# Alim.net
KiCad netlist of a schematic drawn in Altium Designer
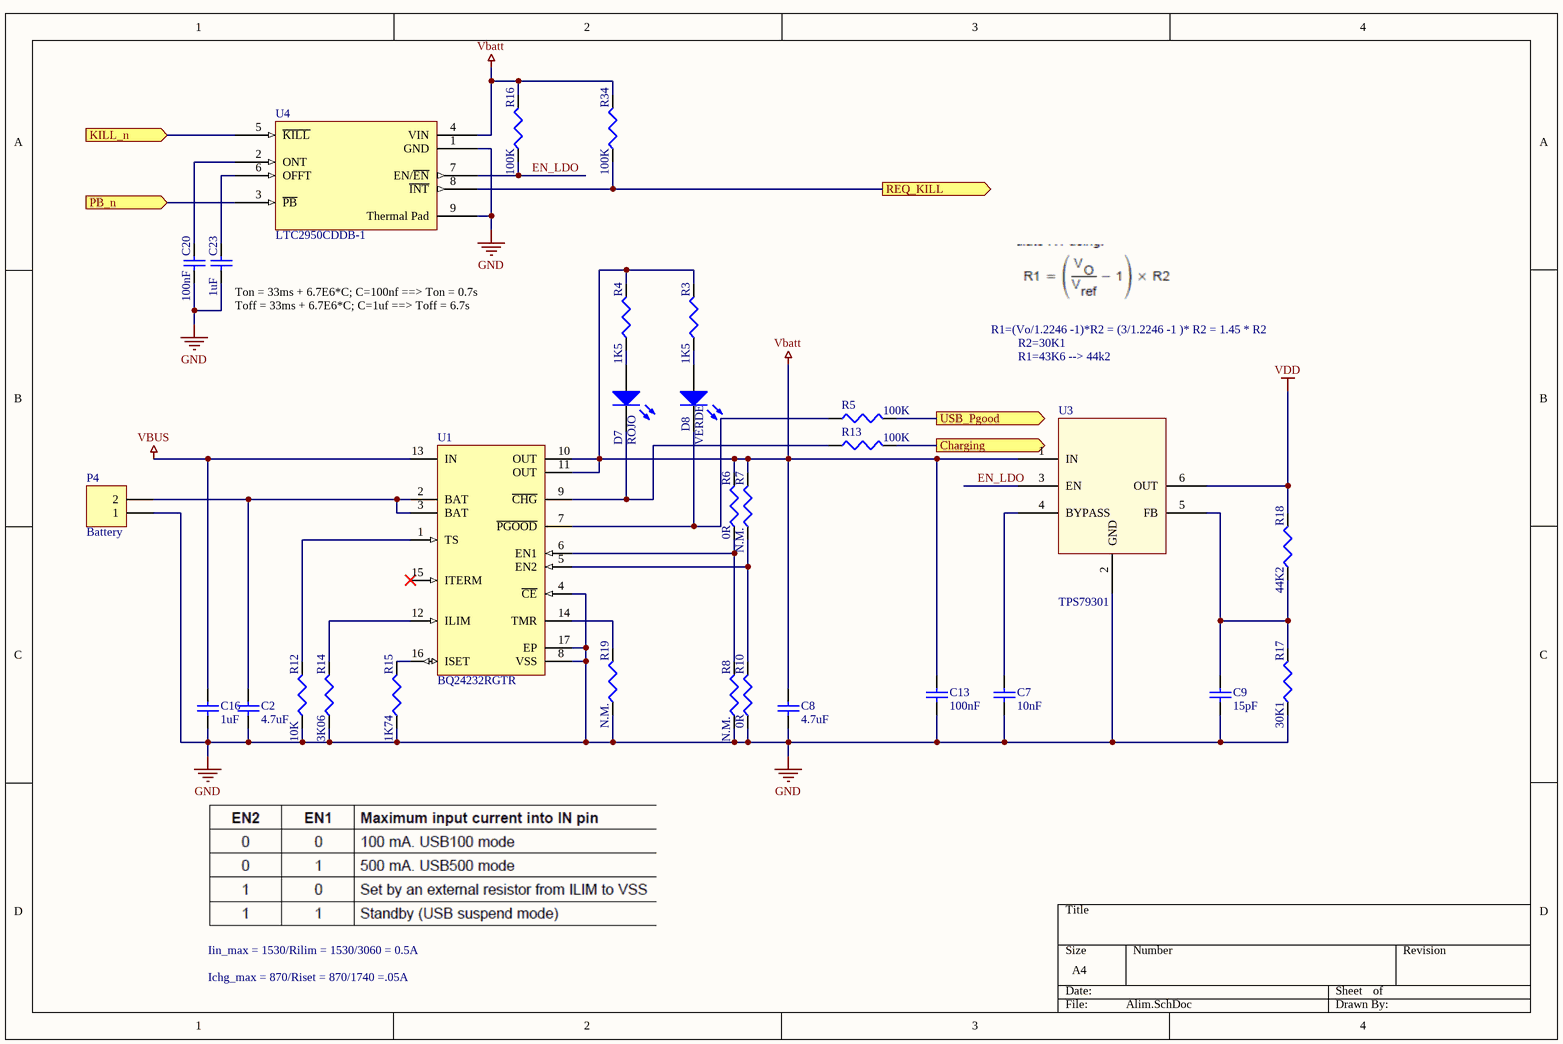
[diagram p0: Alim.SchDoc]

(export (version "E")
  (design (tool "Eeschema 10.0.6"))
  (components
    (comp (ref "C2")
      (value "4.7uF")
      (footprint "C0805")
      (description "Capacitor")
      (fields
        (field (name "MANUFACTURER") "FARNELL")
        (field (name "Comment") "Cap")
        (field (name "PUBLISHER") "Altium Limited")
      )
      (libsource (lib "Miscellaneous Devices") (part "Cap"))
    )
    (comp (ref "C7")
      (value "10nF")
      (footprint "0402")
      (description "Capacitor")
      (fields
        (field (name "MANUFACTURER") "FARNELL")
        (field (name "Comment") "Cap")
        (field (name "PUBLISHER") "Altium Limited")
      )
      (libsource (lib "Miscellaneous Devices") (part "Cap"))
    )
    (comp (ref "C8")
      (value "4.7uF")
      (footprint "C0805")
      (description "Capacitor")
      (fields
        (field (name "MANUFACTURER") "FARNELL")
        (field (name "Comment") "Cap")
        (field (name "PUBLISHER") "Altium Limited")
      )
      (libsource (lib "Miscellaneous Devices") (part "Cap"))
    )
    (comp (ref "C9")
      (value "15pF")
      (footprint "0402")
      (description "Capacitor")
      (fields
        (field (name "MANUFACTURER") "FARNELL")
        (field (name "Comment") "Cap")
        (field (name "PUBLISHER") "Altium Limited")
      )
      (libsource (lib "Miscellaneous Devices") (part "Cap"))
    )
    (comp (ref "C13")
      (value "100nF")
      (footprint "0402")
      (description "Capacitor")
      (fields
        (field (name "MANUFACTURER") "FARNELL")
        (field (name "Comment") "Cap")
        (field (name "PUBLISHER") "Altium Limited")
      )
      (libsource (lib "Miscellaneous Devices") (part "Cap"))
    )
    (comp (ref "C16")
      (value "1uF")
      (footprint "C0805")
      (description "Capacitor")
      (fields
        (field (name "MANUFACTURER") "FARNELL")
        (field (name "Comment") "Cap")
        (field (name "PUBLISHER") "Altium Limited")
      )
      (libsource (lib "Miscellaneous Devices") (part "Cap"))
    )
    (comp (ref "C20")
      (value "100nF")
      (footprint "0402")
      (description "Capacitor")
      (fields
        (field (name "MANUFACTURER") "FARNELL")
        (field (name "Comment") "Cap")
        (field (name "PUBLISHER") "Altium Limited")
      )
      (libsource (lib "Miscellaneous Devices") (part "Cap"))
    )
    (comp (ref "C23")
      (value "1uF")
      (footprint "C0805")
      (description "Capacitor")
      (fields
        (field (name "MANUFACTURER") "FARNELL")
        (field (name "Comment") "Cap")
        (field (name "PUBLISHER") "Altium Limited")
      )
      (libsource (lib "Miscellaneous Devices") (part "Cap"))
    )
    (comp (ref "D7")
      (value "ROJO")
      (footprint "led_0805")
      (description "Typical RED, GREEN, YELLOW, AMBER GaAs LED")
      (fields (field (name "MANUFACTURER") "Smart Prototyping"))
      (libsource (lib "Miscellaneous Devices") (part "LED2"))
    )
    (comp (ref "D8")
      (value "VERDE")
      (footprint "led_0805")
      (description "Typical RED, GREEN, YELLOW, AMBER GaAs LED")
      (fields (field (name "MANUFACTURER") "Smart Prototyping"))
      (libsource (lib "Miscellaneous Devices") (part "LED2"))
    )
    (comp (ref "P4")
      (value "Battery")
      (footprint "MOLEX_5268-2")
      (description "Header, 2-Pin")
      (fields (field (name "MANUFACTURER") "FARNELL") (field (name "PUBLISHER") "Altium Limited"))
      (libsource (lib "Miscellaneous Connectors") (part "Header 2"))
    )
    (comp (ref "R3")
      (value "1K5")
      (footprint "J1-0603")
      (description "Resistor")
      (fields
        (field (name "MANUFACTURER") "FARNELL")
        (field (name "Comment") "Res3")
        (field (name "PUBLISHER") "Altium Limited")
      )
      (libsource (lib "Miscellaneous Devices") (part "Res3"))
    )
    (comp (ref "R4")
      (value "1K5")
      (footprint "J1-0603")
      (description "Resistor")
      (fields
        (field (name "MANUFACTURER") "FARNELL")
        (field (name "Comment") "Res3")
        (field (name "PUBLISHER") "Altium Limited")
      )
      (libsource (lib "Miscellaneous Devices") (part "Res3"))
    )
    (comp (ref "R5")
      (value "100K")
      (footprint "J1-0603")
      (description "Resistor")
      (fields
        (field (name "MANUFACTURER") "FARNELL")
        (field (name "Comment") "Res3")
        (field (name "PUBLISHER") "Altium Limited")
      )
      (libsource (lib "Miscellaneous Devices") (part "Res3"))
    )
    (comp (ref "R6")
      (value "0R")
      (footprint "J1-0603")
      (description "Resistor")
      (fields
        (field (name "MANUFACTURER") "FARNELL")
        (field (name "Comment") "Res3")
        (field (name "PUBLISHER") "Altium Limited")
      )
      (libsource (lib "Miscellaneous Devices") (part "Res3"))
    )
    (comp (ref "R7")
      (value "N.M.")
      (footprint "J1-0603")
      (description "Resistor")
      (fields (field (name "Comment") "Res3") (field (name "PUBLISHER") "Altium Limited"))
      (libsource (lib "Miscellaneous Devices") (part "Res3"))
    )
    (comp (ref "R8")
      (value "N.M.")
      (footprint "J1-0603")
      (description "Resistor")
      (fields (field (name "Comment") "Res3") (field (name "PUBLISHER") "Altium Limited"))
      (libsource (lib "Miscellaneous Devices") (part "Res3"))
    )
    (comp (ref "R10")
      (value "0R")
      (footprint "J1-0603")
      (description "Resistor")
      (fields
        (field (name "MANUFACTURER") "FARNELL")
        (field (name "Comment") "Res3")
        (field (name "PUBLISHER") "Altium Limited")
      )
      (libsource (lib "Miscellaneous Devices") (part "Res3"))
    )
    (comp (ref "R12")
      (value "10K")
      (footprint "J1-0603")
      (description "Resistor")
      (fields
        (field (name "MANUFACTURER") "FARNELL")
        (field (name "Comment") "Res3")
        (field (name "PUBLISHER") "Altium Limited")
      )
      (libsource (lib "Miscellaneous Devices") (part "Res3"))
    )
    (comp (ref "R13")
      (value "100K")
      (footprint "J1-0603")
      (description "Resistor")
      (fields
        (field (name "MANUFACTURER") "FARNELL")
        (field (name "Comment") "Res3")
        (field (name "PUBLISHER") "Altium Limited")
      )
      (libsource (lib "Miscellaneous Devices") (part "Res3"))
    )
    (comp (ref "R14")
      (value "3K06")
      (footprint "J1-0603")
      (description "Resistor")
      (fields
        (field (name "MANUFACTURER") "FARNELL")
        (field (name "Comment") "Res3")
        (field (name "PUBLISHER") "Altium Limited")
      )
      (libsource (lib "Miscellaneous Devices") (part "Res3"))
    )
    (comp (ref "R15")
      (value "1K74")
      (footprint "J1-0603")
      (description "Resistor")
      (fields
        (field (name "MANUFACTURER") "FARNELL")
        (field (name "Comment") "Res3")
        (field (name "PUBLISHER") "Altium Limited")
      )
      (libsource (lib "Miscellaneous Devices") (part "Res3"))
    )
    (comp (ref "R16")
      (value "100K")
      (footprint "J1-0603")
      (description "Resistor")
      (fields
        (field (name "MANUFACTURER") "FARNELL")
        (field (name "Comment") "Res3")
        (field (name "PUBLISHER") "Altium Limited")
      )
      (libsource (lib "Miscellaneous Devices") (part "Res3"))
    )
    (comp (ref "R17")
      (value "30K1")
      (footprint "J1-0603")
      (description "Resistor")
      (fields
        (field (name "MANUFACTURER") "FARNELL")
        (field (name "Comment") "Res3")
        (field (name "PUBLISHER") "Altium Limited")
      )
      (libsource (lib "Miscellaneous Devices") (part "Res3"))
    )
    (comp (ref "R18")
      (value "44K2")
      (footprint "J1-0603")
      (description "Resistor")
      (fields
        (field (name "MANUFACTURER") "FARNELL")
        (field (name "Comment") "Res3")
        (field (name "PUBLISHER") "Altium Limited")
      )
      (libsource (lib "Miscellaneous Devices") (part "Res3"))
    )
    (comp (ref "R19")
      (value "N.M.")
      (footprint "J1-0603")
      (description "Resistor")
      (fields (field (name "Comment") "Res3") (field (name "PUBLISHER") "Altium Limited"))
      (libsource (lib "Miscellaneous Devices") (part "Res3"))
    )
    (comp (ref "R34")
      (value "100K")
      (footprint "J1-0603")
      (description "Resistor")
      (fields
        (field (name "MANUFACTURER") "FARNELL")
        (field (name "Comment") "Res3")
        (field (name "PUBLISHER") "Altium Limited")
      )
      (libsource (lib "Miscellaneous Devices") (part "Res3"))
    )
    (comp (ref "U1")
      (value "BQ24232RGTR")
      (footprint "RGT16-1700X1700TP_SP")
      (fields (field (name "MANUFACTURER") "FARNELL"))
      (libsource (lib "TI Power Management Battery Management") (part "BQ24232RGTR"))
    )
    (comp (ref "U3")
      (value "TPS79301")
      (footprint "SOT26A-6M")
      (fields (field (name "MANUFACTURER") "FARNELL"))
      (libsource (lib "MDAP") (part "TPS79301"))
    )
    (comp (ref "U4")
      (value "LTC2950CDDB-1")
      (footprint "DDB8")
      (description "Push Button On/Off Controller")
      (fields (field (name "MANUFACTURER") "FARNELL") (field (name "PUBLISHER") "Altium Limited"))
      (libsource (lib "LT Peripheral Switch Controller") (part "LTC2950CDDB-1"))
    )
  )
  (nets
    (net (code "1") (name "/Charging") (class "Default")
      (node (ref "R13") (pin "2") (pinfunction "2_2") (pintype "passive"))
    )
    (net (code "2") (name "/EN_LDO") (class "Default")
      (node (ref "R16") (pin "1") (pinfunction "1_1") (pintype "passive"))
      (node (ref "U3") (pin "3") (pinfunction "EN_3") (pintype "passive"))
      (node (ref "U4") (pin "7") (pinfunction "EN/~{EN}_7") (pintype "output"))
    )
    (net (code "3") (name "/KILL_n") (class "Default")
      (node (ref "U4") (pin "5") (pinfunction "~{KILL}_5") (pintype "input"))
    )
    (net (code "4") (name "/PB_n") (class "Default")
      (node (ref "U4") (pin "3") (pinfunction "~{PB}_3") (pintype "input"))
    )
    (net (code "5") (name "/REQ_KILL") (class "Default")
      (node (ref "R34") (pin "1") (pinfunction "1_1") (pintype "passive"))
      (node (ref "U4") (pin "8") (pinfunction "~{INT}_8") (pintype "output"))
    )
    (net (code "6") (name "/USB_Pgood") (class "Default")
      (node (ref "R5") (pin "2") (pinfunction "2_2") (pintype "passive"))
    )
    (net (code "7") (name "GND") (class "Default")
      (node (ref "C13") (pin "1") (pinfunction "1_1") (pintype "passive"))
      (node (ref "C16") (pin "1") (pinfunction "1_1") (pintype "passive"))
      (node (ref "C2") (pin "1") (pinfunction "1_1") (pintype "passive"))
      (node (ref "C20") (pin "1") (pinfunction "1_1") (pintype "passive"))
      (node (ref "C23") (pin "1") (pinfunction "1_1") (pintype "passive"))
      (node (ref "C7") (pin "1") (pinfunction "1_1") (pintype "passive"))
      (node (ref "C8") (pin "1") (pinfunction "1_1") (pintype "passive"))
      (node (ref "C9") (pin "1") (pinfunction "1_1") (pintype "passive"))
      (node (ref "P4") (pin "1") (pinfunction "1_1") (pintype "passive"))
      (node (ref "R10") (pin "1") (pinfunction "1_1") (pintype "passive"))
      (node (ref "R12") (pin "1") (pinfunction "1_1") (pintype "passive"))
      (node (ref "R14") (pin "1") (pinfunction "1_1") (pintype "passive"))
      (node (ref "R15") (pin "1") (pinfunction "1_1") (pintype "passive"))
      (node (ref "R17") (pin "1") (pinfunction "1_1") (pintype "passive"))
      (node (ref "R19") (pin "1") (pinfunction "1_1") (pintype "passive"))
      (node (ref "R8") (pin "1") (pinfunction "1_1") (pintype "passive"))
      (node (ref "U1") (pin "17") (pinfunction "EP_17") (pintype "power_in"))
      (node (ref "U1") (pin "4") (pinfunction "~{CE}_4") (pintype "input"))
      (node (ref "U1") (pin "8") (pinfunction "VSS_8") (pintype "power_in"))
      (node (ref "U3") (pin "2") (pinfunction "GND_2") (pintype "passive"))
      (node (ref "U4") (pin "1") (pinfunction "GND_1") (pintype "power_in"))
      (node (ref "U4") (pin "9") (pinfunction "Thermal_Pad_9") (pintype "passive"))
    )
    (net (code "8") (name "Net-(C2-Pad2)") (class "Default")
      (node (ref "C2") (pin "2") (pinfunction "2_2") (pintype "passive"))
      (node (ref "P4") (pin "2") (pinfunction "2_2") (pintype "passive"))
      (node (ref "U1") (pin "2") (pinfunction "BAT_2") (pintype "power_in"))
      (node (ref "U1") (pin "3") (pinfunction "BAT_3") (pintype "power_in"))
    )
    (net (code "9") (name "Net-(D7-A)") (class "Default")
      (node (ref "D7") (pin "1") (pinfunction "A_1") (pintype "passive"))
      (node (ref "R4") (pin "1") (pinfunction "1_1") (pintype "passive"))
    )
    (net (code "10") (name "Net-(D7-K)") (class "Default")
      (node (ref "D7") (pin "2") (pinfunction "K_2") (pintype "passive"))
      (node (ref "R13") (pin "1") (pinfunction "1_1") (pintype "passive"))
      (node (ref "U1") (pin "9") (pinfunction "~{CHG}_9") (pintype "tri_state"))
    )
    (net (code "11") (name "Net-(D8-A)") (class "Default")
      (node (ref "D8") (pin "1") (pinfunction "A_1") (pintype "passive"))
      (node (ref "R3") (pin "1") (pinfunction "1_1") (pintype "passive"))
    )
    (net (code "12") (name "Net-(D8-K)") (class "Default")
      (node (ref "D8") (pin "2") (pinfunction "K_2") (pintype "passive"))
      (node (ref "R5") (pin "1") (pinfunction "1_1") (pintype "passive"))
      (node (ref "U1") (pin "7") (pinfunction "~{PGOOD}_7") (pintype "tri_state"))
    )
    (net (code "13") (name "Net-(U1-EN1)") (class "Default")
      (node (ref "R6") (pin "1") (pinfunction "1_1") (pintype "passive"))
      (node (ref "R8") (pin "2") (pinfunction "2_2") (pintype "passive"))
      (node (ref "U1") (pin "6") (pinfunction "EN1_6") (pintype "input"))
    )
    (net (code "14") (name "Net-(U1-EN2)") (class "Default")
      (node (ref "R10") (pin "2") (pinfunction "2_2") (pintype "passive"))
      (node (ref "R7") (pin "1") (pinfunction "1_1") (pintype "passive"))
      (node (ref "U1") (pin "5") (pinfunction "EN2_5") (pintype "input"))
    )
    (net (code "15") (name "Net-(U1-ILIM)") (class "Default")
      (node (ref "R14") (pin "2") (pinfunction "2_2") (pintype "passive"))
      (node (ref "U1") (pin "12") (pinfunction "ILIM_12") (pintype "input"))
    )
    (net (code "16") (name "Net-(U1-ISET)") (class "Default")
      (node (ref "R15") (pin "2") (pinfunction "2_2") (pintype "passive"))
      (node (ref "U1") (pin "16") (pinfunction "ISET_16") (pintype "bidirectional"))
    )
    (net (code "17") (name "Net-(U1-TMR)") (class "Default")
      (node (ref "R19") (pin "2") (pinfunction "2_2") (pintype "passive"))
      (node (ref "U1") (pin "14") (pinfunction "TMR_14") (pintype "passive"))
    )
    (net (code "18") (name "Net-(U1-TS)") (class "Default")
      (node (ref "R12") (pin "2") (pinfunction "2_2") (pintype "passive"))
      (node (ref "U1") (pin "1") (pinfunction "TS_1") (pintype "input"))
    )
    (net (code "19") (name "Net-(U3-BYPASS)") (class "Default")
      (node (ref "C7") (pin "2") (pinfunction "2_2") (pintype "passive"))
      (node (ref "U3") (pin "4") (pinfunction "BYPASS_4") (pintype "passive"))
    )
    (net (code "20") (name "Net-(U3-FB)") (class "Default")
      (node (ref "C9") (pin "2") (pinfunction "2_2") (pintype "passive"))
      (node (ref "R17") (pin "2") (pinfunction "2_2") (pintype "passive"))
      (node (ref "R18") (pin "1") (pinfunction "1_1") (pintype "passive"))
      (node (ref "U3") (pin "5") (pinfunction "FB_5") (pintype "passive"))
    )
    (net (code "21") (name "Net-(U4-OFFT)") (class "Default")
      (node (ref "C23") (pin "2") (pinfunction "2_2") (pintype "passive"))
      (node (ref "U4") (pin "6") (pinfunction "OFFT_6") (pintype "input"))
    )
    (net (code "22") (name "Net-(U4-ONT)") (class "Default")
      (node (ref "C20") (pin "2") (pinfunction "2_2") (pintype "passive"))
      (node (ref "U4") (pin "2") (pinfunction "ONT_2") (pintype "input"))
    )
    (net (code "23") (name "VBUS") (class "Default")
      (node (ref "C16") (pin "2") (pinfunction "2_2") (pintype "passive"))
      (node (ref "U1") (pin "13") (pinfunction "IN_13") (pintype "power_in"))
    )
    (net (code "24") (name "VDD") (class "Default")
      (node (ref "R18") (pin "2") (pinfunction "2_2") (pintype "passive"))
      (node (ref "U3") (pin "6") (pinfunction "OUT_6") (pintype "passive"))
    )
    (net (code "25") (name "Vbatt") (class "Default")
      (node (ref "C13") (pin "2") (pinfunction "2_2") (pintype "passive"))
      (node (ref "C8") (pin "2") (pinfunction "2_2") (pintype "passive"))
      (node (ref "R16") (pin "2") (pinfunction "2_2") (pintype "passive"))
      (node (ref "R3") (pin "2") (pinfunction "2_2") (pintype "passive"))
      (node (ref "R34") (pin "2") (pinfunction "2_2") (pintype "passive"))
      (node (ref "R4") (pin "2") (pinfunction "2_2") (pintype "passive"))
      (node (ref "R6") (pin "2") (pinfunction "2_2") (pintype "passive"))
      (node (ref "R7") (pin "2") (pinfunction "2_2") (pintype "passive"))
      (node (ref "U1") (pin "10") (pinfunction "OUT_10") (pintype "power_in"))
      (node (ref "U1") (pin "11") (pinfunction "OUT_11") (pintype "power_in"))
      (node (ref "U3") (pin "1") (pinfunction "IN_1") (pintype "passive"))
      (node (ref "U4") (pin "4") (pinfunction "VIN_4") (pintype "power_in"))
    )
    (net (code "26") (name "unconnected-(U1-ITERM-Pad15)") (class "Default")
      (node (ref "U1") (pin "15") (pinfunction "ITERM_15") (pintype "input+no_connect"))
    )
  )
)
